# pcb_adc.net
KiCad netlist of a schematic drawn in EAGLE
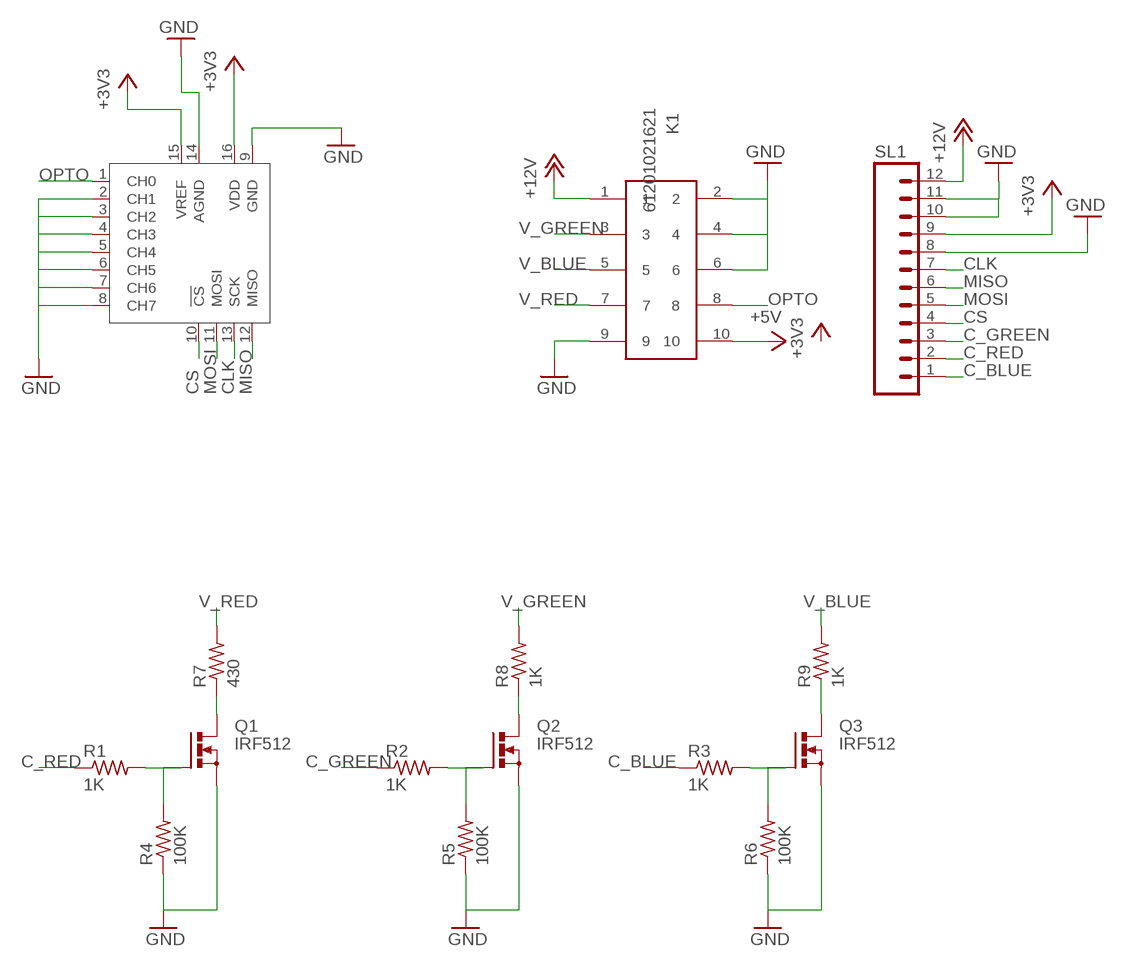
[diagram p0: schematic, sheet 1]

(export (version "E")
  (design (tool "Eeschema 10.0.6"))
  (components
    (comp (ref "K1")
      (value "61201021621")
      (footprint "eagle-import:61201021621")
      (libsource (lib "eagle-import") (part "61201021621"))
    )
    (comp (ref "Q1")
      (value "IRF512")
      (footprint "eagle-import:TO220BV")
      (libsource (lib "eagle-import") (part "IRF512"))
    )
    (comp (ref "Q2")
      (value "IRF512")
      (footprint "eagle-import:TO220BV")
      (libsource (lib "eagle-import") (part "IRF512"))
    )
    (comp (ref "Q3")
      (value "IRF512")
      (footprint "eagle-import:TO220BV")
      (libsource (lib "eagle-import") (part "IRF512"))
    )
    (comp (ref "R1")
      (value "1K")
      (footprint "eagle-import:0204_7")
      (libsource (lib "eagle-import") (part "R-US_0204/7"))
    )
    (comp (ref "R2")
      (value "1K")
      (footprint "eagle-import:0204_7")
      (libsource (lib "eagle-import") (part "R-US_0204/7"))
    )
    (comp (ref "R3")
      (value "1K")
      (footprint "eagle-import:0204_7")
      (libsource (lib "eagle-import") (part "R-US_0204/7"))
    )
    (comp (ref "R4")
      (value "100K")
      (footprint "eagle-import:0204_7")
      (libsource (lib "eagle-import") (part "R-US_0204/7"))
    )
    (comp (ref "R5")
      (value "100K")
      (footprint "eagle-import:0204_7")
      (libsource (lib "eagle-import") (part "R-US_0204/7"))
    )
    (comp (ref "R6")
      (value "100K")
      (footprint "eagle-import:0204_7")
      (libsource (lib "eagle-import") (part "R-US_0204/7"))
    )
    (comp (ref "R7")
      (value "430")
      (footprint "eagle-import:0204_7")
      (libsource (lib "eagle-import") (part "R-US_0204/7"))
    )
    (comp (ref "R8")
      (value "1K")
      (footprint "eagle-import:0204_7")
      (libsource (lib "eagle-import") (part "R-US_0204/7"))
    )
    (comp (ref "R9")
      (value "1K")
      (footprint "eagle-import:0204_7")
      (libsource (lib "eagle-import") (part "R-US_0204/7"))
    )
    (comp (ref "SL1")
      (value "M12")
      (footprint "eagle-import:12P")
      (libsource (lib "eagle-import") (part "M12"))
    )
    (comp (ref "U$1")
      (value "MCP3008P")
      (footprint "eagle-import:DIL16")
      (libsource (lib "eagle-import") (part "MCP3008P"))
    )
  )
  (nets
    (net (code "1") (name "+3V3") (class "Default")
      (node (ref "SL1") (pin "9") (pinfunction "9_9") (pintype "passive"))
      (node (ref "U$1") (pin "15") (pinfunction "VREF_15") (pintype "power_in"))
      (node (ref "U$1") (pin "16") (pinfunction "VDD_16") (pintype "power_in"))
    )
    (net (code "2") (name "+5V") (class "Default")
      (node (ref "K1") (pin "10") (pinfunction "10_10") (pintype "passive"))
    )
    (net (code "3") (name "+12V") (class "Default")
      (node (ref "K1") (pin "1") (pinfunction "1_1") (pintype "passive"))
      (node (ref "SL1") (pin "12") (pinfunction "12_12") (pintype "passive"))
    )
    (net (code "4") (name "/CLK") (class "Default")
      (node (ref "SL1") (pin "7") (pinfunction "7_7") (pintype "passive"))
      (node (ref "U$1") (pin "13") (pinfunction "SCK_13") (pintype "input"))
    )
    (net (code "5") (name "/CS") (class "Default")
      (node (ref "SL1") (pin "4") (pinfunction "4_4") (pintype "passive"))
      (node (ref "U$1") (pin "10") (pinfunction "~{CS}_10") (pintype "input"))
    )
    (net (code "6") (name "/C_BLUE") (class "Default")
      (node (ref "R3") (pin "1") (pinfunction "1_1") (pintype "passive"))
      (node (ref "SL1") (pin "1") (pinfunction "1_1") (pintype "passive"))
    )
    (net (code "7") (name "/C_GREEN") (class "Default")
      (node (ref "R2") (pin "1") (pinfunction "1_1") (pintype "passive"))
      (node (ref "SL1") (pin "3") (pinfunction "3_3") (pintype "passive"))
    )
    (net (code "8") (name "/C_RED") (class "Default")
      (node (ref "R1") (pin "1") (pinfunction "1_1") (pintype "passive"))
      (node (ref "SL1") (pin "2") (pinfunction "2_2") (pintype "passive"))
    )
    (net (code "9") (name "/MISO") (class "Default")
      (node (ref "SL1") (pin "6") (pinfunction "6_6") (pintype "passive"))
      (node (ref "U$1") (pin "12") (pinfunction "MISO_12") (pintype "output"))
    )
    (net (code "10") (name "/MOSI") (class "Default")
      (node (ref "SL1") (pin "5") (pinfunction "5_5") (pintype "passive"))
      (node (ref "U$1") (pin "11") (pinfunction "MOSI_11") (pintype "input"))
    )
    (net (code "11") (name "/OPTO") (class "Default")
      (node (ref "K1") (pin "8") (pinfunction "8_8") (pintype "passive"))
      (node (ref "U$1") (pin "1") (pinfunction "CH0_1") (pintype "input"))
    )
    (net (code "12") (name "/V_BLUE") (class "Default")
      (node (ref "K1") (pin "5") (pinfunction "5_5") (pintype "passive"))
      (node (ref "R9") (pin "2") (pinfunction "2_2") (pintype "passive"))
    )
    (net (code "13") (name "/V_GREEN") (class "Default")
      (node (ref "K1") (pin "3") (pinfunction "3_3") (pintype "passive"))
      (node (ref "R8") (pin "2") (pinfunction "2_2") (pintype "passive"))
    )
    (net (code "14") (name "/V_RED") (class "Default")
      (node (ref "K1") (pin "7") (pinfunction "7_7") (pintype "passive"))
      (node (ref "R7") (pin "2") (pinfunction "2_2") (pintype "passive"))
    )
    (net (code "15") (name "GND") (class "Default")
      (node (ref "K1") (pin "2") (pinfunction "2_2") (pintype "passive"))
      (node (ref "K1") (pin "4") (pinfunction "4_4") (pintype "passive"))
      (node (ref "K1") (pin "6") (pinfunction "6_6") (pintype "passive"))
      (node (ref "K1") (pin "9") (pinfunction "9_9") (pintype "passive"))
      (node (ref "Q1") (pin "S") (pinfunction "S_S") (pintype "passive"))
      (node (ref "Q2") (pin "S") (pinfunction "S_S") (pintype "passive"))
      (node (ref "Q3") (pin "S") (pinfunction "S_S") (pintype "passive"))
      (node (ref "R4") (pin "1") (pinfunction "1_1") (pintype "passive"))
      (node (ref "R5") (pin "1") (pinfunction "1_1") (pintype "passive"))
      (node (ref "R6") (pin "1") (pinfunction "1_1") (pintype "passive"))
      (node (ref "SL1") (pin "10") (pinfunction "10_10") (pintype "passive"))
      (node (ref "SL1") (pin "11") (pinfunction "11_11") (pintype "passive"))
      (node (ref "SL1") (pin "8") (pinfunction "8_8") (pintype "passive"))
      (node (ref "U$1") (pin "14") (pinfunction "AGND_14") (pintype "power_in"))
      (node (ref "U$1") (pin "2") (pinfunction "CH1_2") (pintype "input"))
      (node (ref "U$1") (pin "3") (pinfunction "CH2_3") (pintype "input"))
      (node (ref "U$1") (pin "4") (pinfunction "CH3_4") (pintype "input"))
      (node (ref "U$1") (pin "5") (pinfunction "CH4_5") (pintype "input"))
      (node (ref "U$1") (pin "6") (pinfunction "CH5_6") (pintype "input"))
      (node (ref "U$1") (pin "7") (pinfunction "CH6_7") (pintype "input"))
      (node (ref "U$1") (pin "8") (pinfunction "CH7_8") (pintype "input"))
      (node (ref "U$1") (pin "9") (pinfunction "GND_9") (pintype "power_in"))
    )
    (net (code "16") (name "Net-(Q1-PadD)") (class "Default")
      (node (ref "Q1") (pin "D") (pinfunction "D_D") (pintype "passive"))
      (node (ref "R7") (pin "1") (pinfunction "1_1") (pintype "passive"))
    )
    (net (code "17") (name "Net-(Q1-PadG)") (class "Default")
      (node (ref "Q1") (pin "G") (pinfunction "G_G") (pintype "passive"))
      (node (ref "R1") (pin "2") (pinfunction "2_2") (pintype "passive"))
      (node (ref "R4") (pin "2") (pinfunction "2_2") (pintype "passive"))
    )
    (net (code "18") (name "Net-(Q2-PadD)") (class "Default")
      (node (ref "Q2") (pin "D") (pinfunction "D_D") (pintype "passive"))
      (node (ref "R8") (pin "1") (pinfunction "1_1") (pintype "passive"))
    )
    (net (code "19") (name "Net-(Q2-PadG)") (class "Default")
      (node (ref "Q2") (pin "G") (pinfunction "G_G") (pintype "passive"))
      (node (ref "R2") (pin "2") (pinfunction "2_2") (pintype "passive"))
      (node (ref "R5") (pin "2") (pinfunction "2_2") (pintype "passive"))
    )
    (net (code "20") (name "Net-(Q3-PadD)") (class "Default")
      (node (ref "Q3") (pin "D") (pinfunction "D_D") (pintype "passive"))
      (node (ref "R9") (pin "1") (pinfunction "1_1") (pintype "passive"))
    )
    (net (code "21") (name "Net-(Q3-PadG)") (class "Default")
      (node (ref "Q3") (pin "G") (pinfunction "G_G") (pintype "passive"))
      (node (ref "R3") (pin "2") (pinfunction "2_2") (pintype "passive"))
      (node (ref "R6") (pin "2") (pinfunction "2_2") (pintype "passive"))
    )
  )
)
